# RunningAnalyzer_v1.net
KiCad netlist of a schematic drawn in EAGLE
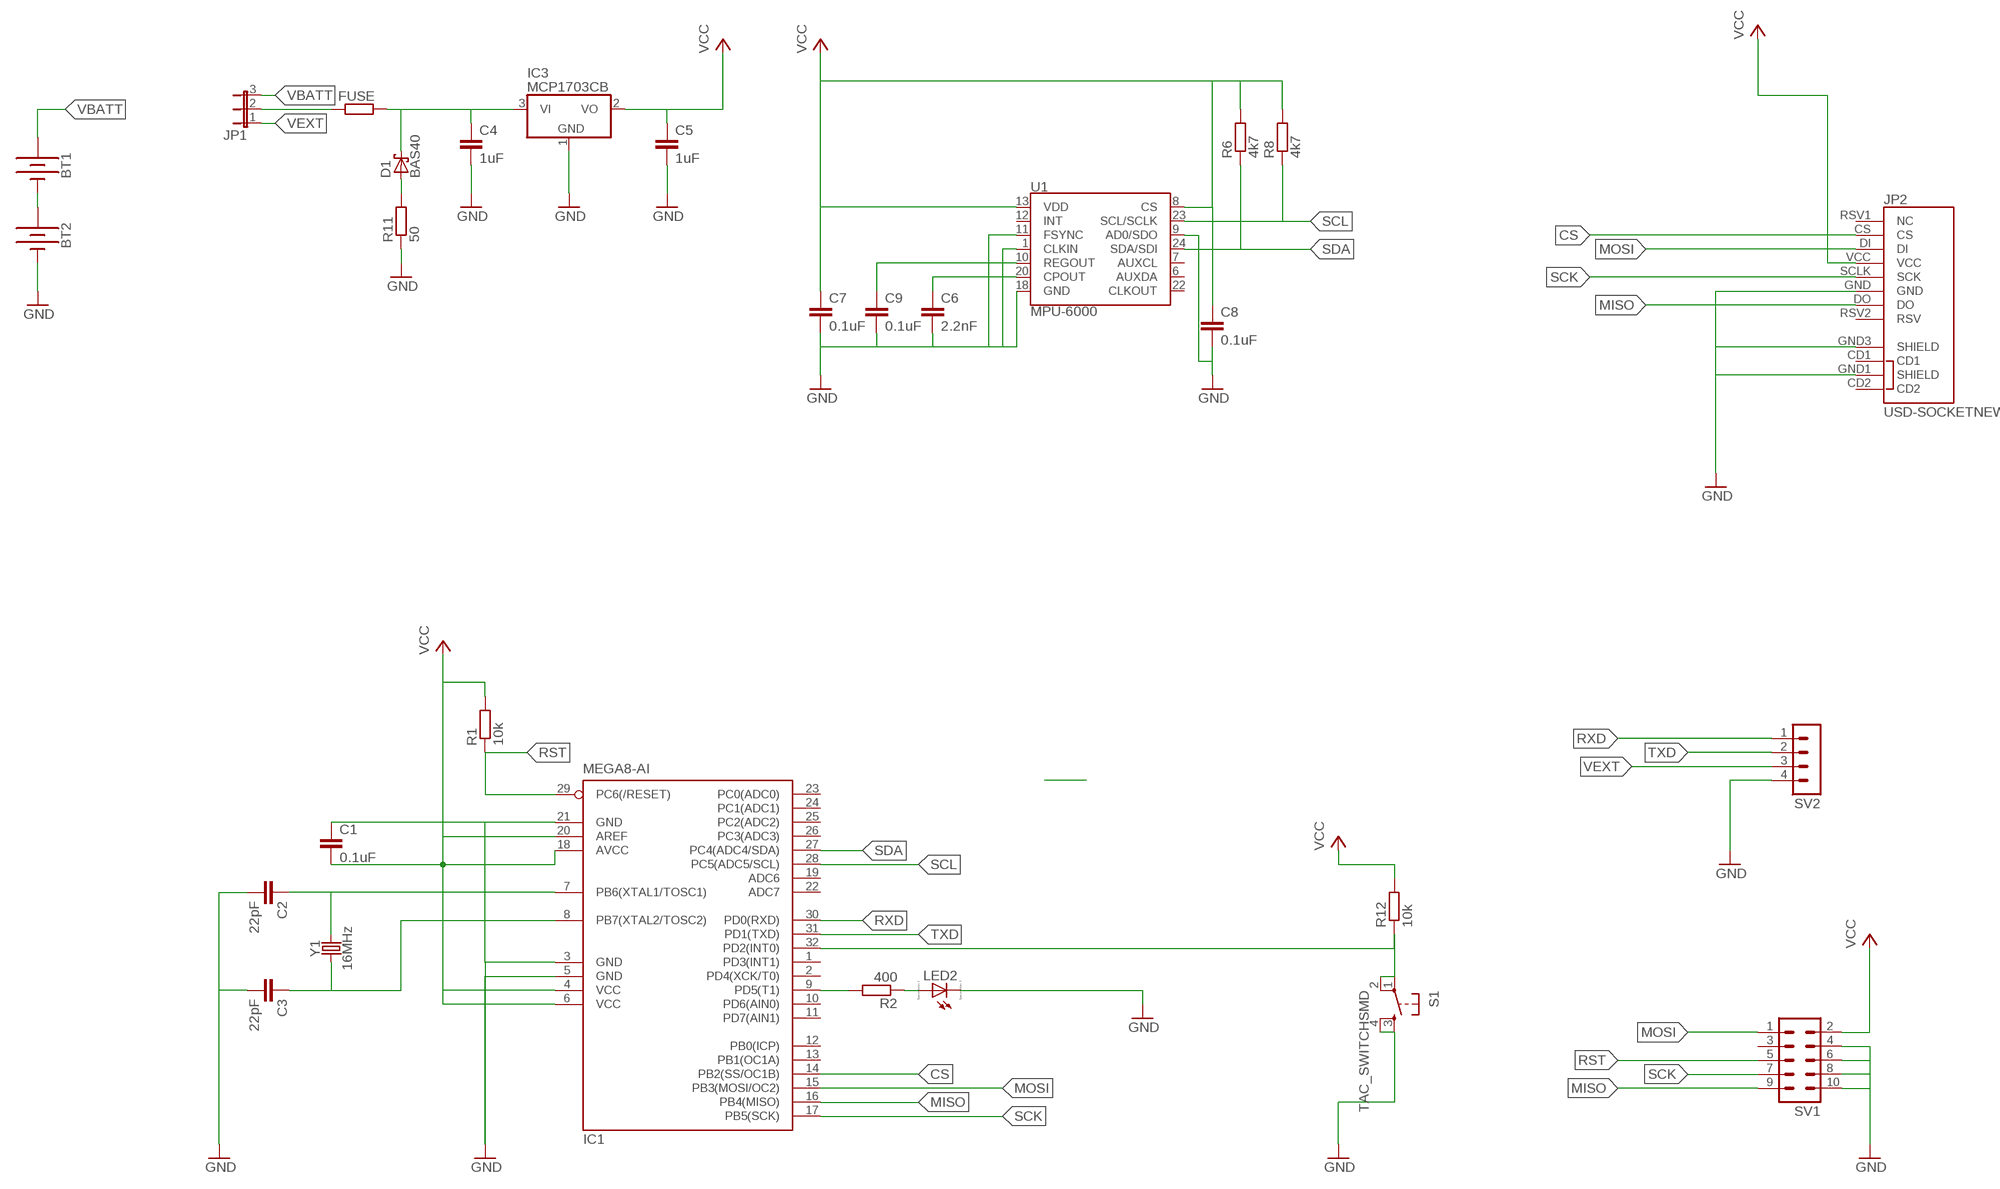
[diagram p0: schematic, sheet 1]

(export (version "E")
  (design (tool "Eeschema 10.0.6"))
  (components
    (comp (ref "BT1")
      (value "BATTERY-20MM_SMD_4LEGS_OVERPASTE")
      (footprint "eagle-import:BATTCON_20MM_4LEGS_OVERPASTE")
      (libsource (lib "eagle-import") (part "BATTERY-20MM_SMD_4LEGS_OVERPASTE"))
    )
    (comp (ref "BT2")
      (value "BATTERY-20MM_SMD_4LEGS_OVERPASTE")
      (footprint "eagle-import:BATTCON_20MM_4LEGS_OVERPASTE")
      (libsource (lib "eagle-import") (part "BATTERY-20MM_SMD_4LEGS_OVERPASTE"))
    )
    (comp (ref "C1")
      (value "0.1uF")
      (footprint "eagle-import:C0805")
      (libsource (lib "eagle-import") (part "C-EUC0805"))
    )
    (comp (ref "C2")
      (value "22pF")
      (footprint "eagle-import:C0805")
      (libsource (lib "eagle-import") (part "C-EUC0805"))
    )
    (comp (ref "C3")
      (value "22pF")
      (footprint "eagle-import:C0805")
      (libsource (lib "eagle-import") (part "C-EUC0805"))
    )
    (comp (ref "C4")
      (value "1uF")
      (footprint "eagle-import:C0805")
      (libsource (lib "eagle-import") (part "C-EUC0805"))
    )
    (comp (ref "C5")
      (value "1uF")
      (footprint "eagle-import:C0805")
      (libsource (lib "eagle-import") (part "C-EUC0805"))
    )
    (comp (ref "C6")
      (value "2.2nF")
      (footprint "eagle-import:C0805")
      (libsource (lib "eagle-import") (part "C-EUC0805"))
    )
    (comp (ref "C7")
      (value "0.1uF")
      (footprint "eagle-import:C0805")
      (libsource (lib "eagle-import") (part "C-EUC0805"))
    )
    (comp (ref "C8")
      (value "0.1uF")
      (footprint "eagle-import:C0805")
      (libsource (lib "eagle-import") (part "C-EUC0805"))
    )
    (comp (ref "C9")
      (value "0.1uF")
      (footprint "eagle-import:C0805")
      (libsource (lib "eagle-import") (part "C-EUC0805"))
    )
    (comp (ref "D1")
      (value "BAS40")
      (footprint "eagle-import:SOT23")
      (libsource (lib "eagle-import") (part "BAS40"))
    )
    (comp (ref "FUSE")
      (value "R-EU_M1206")
      (footprint "eagle-import:M1206")
      (libsource (lib "eagle-import") (part "R-EU_M1206"))
    )
    (comp (ref "IC1")
      (value "MEGA8-AI")
      (footprint "eagle-import:TQFP32-08")
      (fields (field (name "MPN") "ATMEGA8-16AU"))
      (libsource (lib "eagle-import") (part "MEGA8-AI"))
    )
    (comp (ref "IC3")
      (value "MCP1703CB")
      (footprint "eagle-import:SOT23")
      (libsource (lib "eagle-import") (part "MCP1703CB"))
    )
    (comp (ref "JP1")
      (value "JP2E")
      (footprint "eagle-import:JP2")
      (libsource (lib "eagle-import") (part "JP2E"))
    )
    (comp (ref "JP2")
      (value "USD-SOCKETNEW")
      (footprint "eagle-import:MICRO-SD-SOCKET-PP")
      (libsource (lib "eagle-import") (part "USD-SOCKETNEW"))
    )
    (comp (ref "LED2")
      (value "LED_E")
      (footprint "eagle-import:LED_1206")
      (libsource (lib "eagle-import") (part "LED_E"))
    )
    (comp (ref "R1")
      (value "10k")
      (footprint "eagle-import:R1206")
      (libsource (lib "eagle-import") (part "resistor_348_R-EU_R1206"))
    )
    (comp (ref "R2")
      (value "400")
      (footprint "eagle-import:R0805")
      (libsource (lib "eagle-import") (part "R-EU_R0805"))
    )
    (comp (ref "R6")
      (value "4k7")
      (footprint "eagle-import:R0805")
      (libsource (lib "eagle-import") (part "R-EU_R0805"))
    )
    (comp (ref "R8")
      (value "4k7")
      (footprint "eagle-import:R0805")
      (libsource (lib "eagle-import") (part "R-EU_R0805"))
    )
    (comp (ref "R11")
      (value "50")
      (footprint "eagle-import:R0805")
      (libsource (lib "eagle-import") (part "R-EU_R0805"))
    )
    (comp (ref "R12")
      (value "10k")
      (footprint "eagle-import:R1206")
      (libsource (lib "eagle-import") (part "resistor_348_R-EU_R1206"))
    )
    (comp (ref "S1")
      (value "TAC_SWITCHSMD")
      (footprint "eagle-import:TACTILE-SWITCH-SMD")
      (libsource (lib "eagle-import") (part "TAC_SWITCHSMD"))
    )
    (comp (ref "SV1")
      (value "MA05-2")
      (footprint "eagle-import:MA05-2")
      (libsource (lib "eagle-import") (part "MA05-2"))
    )
    (comp (ref "SV2")
      (value "MA04-1")
      (footprint "eagle-import:MA04-1")
      (libsource (lib "eagle-import") (part "MA04-1"))
    )
    (comp (ref "U1")
      (value "MPU-6000")
      (footprint "eagle-import:QFN-24-EP")
      (libsource (lib "eagle-import") (part "MPU-6000"))
    )
    (comp (ref "Y1")
      (value "16MHz")
      (footprint "eagle-import:HC49UP")
      (libsource (lib "eagle-import") (part "CRYSTALSMD-HC49UP"))
    )
  )
  (nets
    (net (code "1") (name "CS") (class "Default")
      (node (ref "IC1") (pin "14") (pinfunction "PB2(SS/OC1B)_14") (pintype "bidirectional"))
      (node (ref "JP2") (pin "CS") (pinfunction "CS_CS") (pintype "bidirectional"))
    )
    (net (code "2") (name "GND") (class "Default")
      (node (ref "BT2") (pin "2") (pinfunction "-_2") (pintype "power_in"))
      (node (ref "C1") (pin "1") (pinfunction "1_1") (pintype "passive"))
      (node (ref "C2") (pin "2") (pinfunction "2_2") (pintype "passive"))
      (node (ref "C3") (pin "2") (pinfunction "2_2") (pintype "passive"))
      (node (ref "C4") (pin "2") (pinfunction "2_2") (pintype "passive"))
      (node (ref "C5") (pin "2") (pinfunction "2_2") (pintype "passive"))
      (node (ref "C6") (pin "2") (pinfunction "2_2") (pintype "passive"))
      (node (ref "C7") (pin "2") (pinfunction "2_2") (pintype "passive"))
      (node (ref "C8") (pin "2") (pinfunction "2_2") (pintype "passive"))
      (node (ref "C9") (pin "2") (pinfunction "2_2") (pintype "passive"))
      (node (ref "IC1") (pin "21") (pinfunction "GND_21") (pintype "power_in"))
      (node (ref "IC1") (pin "3") (pinfunction "GND_3") (pintype "power_in"))
      (node (ref "IC1") (pin "5") (pinfunction "GND_5") (pintype "power_in"))
      (node (ref "IC3") (pin "1") (pinfunction "GND_1") (pintype "passive"))
      (node (ref "JP2") (pin "GND") (pinfunction "GND_GND") (pintype "bidirectional"))
      (node (ref "JP2") (pin "GND1") (pinfunction "SHIELD_GND1") (pintype "bidirectional"))
      (node (ref "JP2") (pin "GND3") (pinfunction "SHIELD_GND3") (pintype "bidirectional"))
      (node (ref "LED2") (pin "C") (pinfunction "C_C") (pintype "passive"))
      (node (ref "R11") (pin "1") (pinfunction "1_1") (pintype "passive"))
      (node (ref "S1") (pin "3") (pinfunction "3_3") (pintype "passive"))
      (node (ref "S1") (pin "4") (pinfunction "4_4") (pintype "passive"))
      (node (ref "SV1") (pin "10") (pinfunction "10_10") (pintype "passive"))
      (node (ref "SV1") (pin "4") (pinfunction "4_4") (pintype "passive"))
      (node (ref "SV1") (pin "6") (pinfunction "6_6") (pintype "passive"))
      (node (ref "SV1") (pin "8") (pinfunction "8_8") (pintype "passive"))
      (node (ref "SV2") (pin "4") (pinfunction "4_4") (pintype "passive"))
      (node (ref "U1") (pin "1") (pinfunction "CLKIN_1") (pintype "bidirectional"))
      (node (ref "U1") (pin "11") (pinfunction "FSYNC_11") (pintype "bidirectional"))
      (node (ref "U1") (pin "18") (pinfunction "GND_18") (pintype "bidirectional"))
      (node (ref "U1") (pin "9") (pinfunction "AD0/SDO_9") (pintype "bidirectional"))
    )
    (net (code "3") (name "MISO") (class "Default")
      (node (ref "IC1") (pin "16") (pinfunction "PB4(MISO)_16") (pintype "bidirectional"))
      (node (ref "JP2") (pin "DO") (pinfunction "DO_DO") (pintype "bidirectional"))
      (node (ref "SV1") (pin "9") (pinfunction "9_9") (pintype "passive"))
    )
    (net (code "4") (name "MOSI") (class "Default")
      (node (ref "IC1") (pin "15") (pinfunction "PB3(MOSI/OC2)_15") (pintype "bidirectional"))
      (node (ref "JP2") (pin "DI") (pinfunction "DI_DI") (pintype "bidirectional"))
      (node (ref "SV1") (pin "1") (pinfunction "1_1") (pintype "passive"))
    )
    (net (code "5") (name "Net-(BT1--)") (class "Default")
      (node (ref "BT1") (pin "2") (pinfunction "-_2") (pintype "power_in"))
      (node (ref "BT2") (pin "1") (pinfunction "+_1") (pintype "power_in"))
    )
    (net (code "6") (name "Net-(D1-A)") (class "Default")
      (node (ref "D1") (pin "1") (pinfunction "A_1") (pintype "passive"))
      (node (ref "R11") (pin "2") (pinfunction "2_2") (pintype "passive"))
    )
    (net (code "7") (name "Net-(D1-C)") (class "Default")
      (node (ref "C4") (pin "1") (pinfunction "1_1") (pintype "passive"))
      (node (ref "D1") (pin "3") (pinfunction "C_3") (pintype "passive"))
      (node (ref "FUSE") (pin "2") (pinfunction "2_2") (pintype "passive"))
      (node (ref "IC3") (pin "3") (pinfunction "VI_3") (pintype "input"))
    )
    (net (code "8") (name "Net-(FUSE-Pad1)") (class "Default")
      (node (ref "FUSE") (pin "1") (pinfunction "1_1") (pintype "passive"))
      (node (ref "JP1") (pin "2") (pinfunction "2_2") (pintype "passive"))
    )
    (net (code "9") (name "Net-(IC1-PB6(XTAL1{slash}TOSC1))") (class "Default")
      (node (ref "C2") (pin "1") (pinfunction "1_1") (pintype "passive"))
      (node (ref "IC1") (pin "7") (pinfunction "PB6(XTAL1/TOSC1)_7") (pintype "bidirectional"))
      (node (ref "Y1") (pin "2") (pinfunction "2_2") (pintype "passive"))
    )
    (net (code "10") (name "Net-(IC1-PB7(XTAL2{slash}TOSC2))") (class "Default")
      (node (ref "C3") (pin "1") (pinfunction "1_1") (pintype "passive"))
      (node (ref "IC1") (pin "8") (pinfunction "PB7(XTAL2/TOSC2)_8") (pintype "bidirectional"))
      (node (ref "Y1") (pin "1") (pinfunction "1_1") (pintype "passive"))
    )
    (net (code "11") (name "Net-(IC1-PD2(INT0))") (class "Default")
      (node (ref "IC1") (pin "32") (pinfunction "PD2(INT0)_32") (pintype "bidirectional"))
      (node (ref "R12") (pin "1") (pinfunction "1_1") (pintype "passive"))
      (node (ref "S1") (pin "1") (pinfunction "1_1") (pintype "passive"))
      (node (ref "S1") (pin "2") (pinfunction "2_2") (pintype "passive"))
    )
    (net (code "12") (name "Net-(IC1-PD5(T1))") (class "Default")
      (node (ref "IC1") (pin "9") (pinfunction "PD5(T1)_9") (pintype "bidirectional"))
      (node (ref "R2") (pin "2") (pinfunction "2_2") (pintype "passive"))
    )
    (net (code "13") (name "Net-(LED2-PadA)") (class "Default")
      (node (ref "LED2") (pin "A") (pinfunction "A_A") (pintype "passive"))
      (node (ref "R2") (pin "1") (pinfunction "1_1") (pintype "passive"))
    )
    (net (code "14") (name "Net-(U1-CPOUT)") (class "Default")
      (node (ref "C6") (pin "1") (pinfunction "1_1") (pintype "passive"))
      (node (ref "U1") (pin "20") (pinfunction "CPOUT_20") (pintype "bidirectional"))
    )
    (net (code "15") (name "Net-(U1-REGOUT)") (class "Default")
      (node (ref "C9") (pin "1") (pinfunction "1_1") (pintype "passive"))
      (node (ref "U1") (pin "10") (pinfunction "REGOUT_10") (pintype "bidirectional"))
    )
    (net (code "16") (name "RST") (class "Default")
      (node (ref "IC1") (pin "29") (pinfunction "PC6(/RESET)_29") (pintype "bidirectional"))
      (node (ref "R1") (pin "1") (pinfunction "1_1") (pintype "passive"))
      (node (ref "SV1") (pin "5") (pinfunction "5_5") (pintype "passive"))
    )
    (net (code "17") (name "RXD") (class "Default")
      (node (ref "IC1") (pin "30") (pinfunction "PD0(RXD)_30") (pintype "bidirectional"))
      (node (ref "SV2") (pin "1") (pinfunction "1_1") (pintype "passive"))
    )
    (net (code "18") (name "SCK") (class "Default")
      (node (ref "IC1") (pin "17") (pinfunction "PB5(SCK)_17") (pintype "bidirectional"))
      (node (ref "JP2") (pin "SCLK") (pinfunction "SCK_SCLK") (pintype "bidirectional"))
      (node (ref "SV1") (pin "7") (pinfunction "7_7") (pintype "passive"))
    )
    (net (code "19") (name "SCL") (class "Default")
      (node (ref "IC1") (pin "28") (pinfunction "PC5(ADC5/SCL)_28") (pintype "bidirectional"))
      (node (ref "R8") (pin "1") (pinfunction "1_1") (pintype "passive"))
      (node (ref "U1") (pin "23") (pinfunction "SCL/SCLK_23") (pintype "bidirectional"))
    )
    (net (code "20") (name "SDA") (class "Default")
      (node (ref "IC1") (pin "27") (pinfunction "PC4(ADC4/SDA)_27") (pintype "bidirectional"))
      (node (ref "R6") (pin "1") (pinfunction "1_1") (pintype "passive"))
      (node (ref "U1") (pin "24") (pinfunction "SDA/SDI_24") (pintype "bidirectional"))
    )
    (net (code "21") (name "TXD") (class "Default")
      (node (ref "IC1") (pin "31") (pinfunction "PD1(TXD)_31") (pintype "bidirectional"))
      (node (ref "SV2") (pin "2") (pinfunction "2_2") (pintype "passive"))
    )
    (net (code "22") (name "VBATT") (class "Default")
      (node (ref "BT1") (pin "1") (pinfunction "+_1") (pintype "power_in"))
      (node (ref "JP1") (pin "3") (pinfunction "3_3") (pintype "passive"))
    )
    (net (code "23") (name "VCC") (class "Default")
      (node (ref "C1") (pin "2") (pinfunction "2_2") (pintype "passive"))
      (node (ref "C5") (pin "1") (pinfunction "1_1") (pintype "passive"))
      (node (ref "C7") (pin "1") (pinfunction "1_1") (pintype "passive"))
      (node (ref "C8") (pin "1") (pinfunction "1_1") (pintype "passive"))
      (node (ref "IC1") (pin "18") (pinfunction "AVCC_18") (pintype "power_in"))
      (node (ref "IC1") (pin "20") (pinfunction "AREF_20") (pintype "passive"))
      (node (ref "IC1") (pin "4") (pinfunction "VCC_4") (pintype "power_in"))
      (node (ref "IC1") (pin "6") (pinfunction "VCC_6") (pintype "power_in"))
      (node (ref "IC3") (pin "2") (pinfunction "VO_2") (pintype "passive"))
      (node (ref "JP2") (pin "VCC") (pinfunction "VCC_VCC") (pintype "bidirectional"))
      (node (ref "R1") (pin "2") (pinfunction "2_2") (pintype "passive"))
      (node (ref "R12") (pin "2") (pinfunction "2_2") (pintype "passive"))
      (node (ref "R6") (pin "2") (pinfunction "2_2") (pintype "passive"))
      (node (ref "R8") (pin "2") (pinfunction "2_2") (pintype "passive"))
      (node (ref "SV1") (pin "2") (pinfunction "2_2") (pintype "passive"))
      (node (ref "U1") (pin "13") (pinfunction "VDD_13") (pintype "bidirectional"))
      (node (ref "U1") (pin "8") (pinfunction "CS_8") (pintype "bidirectional"))
    )
    (net (code "24") (name "VEXT") (class "Default")
      (node (ref "JP1") (pin "1") (pinfunction "1_1") (pintype "passive"))
      (node (ref "SV2") (pin "3") (pinfunction "3_3") (pintype "passive"))
    )
    (net (code "25") (name "unconnected-(IC1-ADC6-Pad19)") (class "Default")
      (node (ref "IC1") (pin "19") (pinfunction "ADC6_19") (pintype "bidirectional"))
    )
    (net (code "26") (name "unconnected-(IC1-ADC7-Pad22)") (class "Default")
      (node (ref "IC1") (pin "22") (pinfunction "ADC7_22") (pintype "bidirectional"))
    )
    (net (code "27") (name "unconnected-(IC1-PB0(ICP)-Pad12)") (class "Default")
      (node (ref "IC1") (pin "12") (pinfunction "PB0(ICP)_12") (pintype "bidirectional"))
    )
    (net (code "28") (name "unconnected-(IC1-PB1(OC1A)-Pad13)") (class "Default")
      (node (ref "IC1") (pin "13") (pinfunction "PB1(OC1A)_13") (pintype "bidirectional"))
    )
    (net (code "29") (name "unconnected-(IC1-PC0(ADC0)-Pad23)") (class "Default")
      (node (ref "IC1") (pin "23") (pinfunction "PC0(ADC0)_23") (pintype "bidirectional"))
    )
    (net (code "30") (name "unconnected-(IC1-PC1(ADC1)-Pad24)") (class "Default")
      (node (ref "IC1") (pin "24") (pinfunction "PC1(ADC1)_24") (pintype "bidirectional"))
    )
    (net (code "31") (name "unconnected-(IC1-PC2(ADC2)-Pad25)") (class "Default")
      (node (ref "IC1") (pin "25") (pinfunction "PC2(ADC2)_25") (pintype "bidirectional"))
    )
    (net (code "32") (name "unconnected-(IC1-PC3(ADC3)-Pad26)") (class "Default")
      (node (ref "IC1") (pin "26") (pinfunction "PC3(ADC3)_26") (pintype "bidirectional"))
    )
    (net (code "33") (name "unconnected-(IC1-PD3(INT1)-Pad1)") (class "Default")
      (node (ref "IC1") (pin "1") (pinfunction "PD3(INT1)_1") (pintype "bidirectional"))
    )
    (net (code "34") (name "unconnected-(IC1-PD4(XCK{slash}T0)-Pad2)") (class "Default")
      (node (ref "IC1") (pin "2") (pinfunction "PD4(XCK/T0)_2") (pintype "bidirectional"))
    )
    (net (code "35") (name "unconnected-(IC1-PD6(AIN0)-Pad10)") (class "Default")
      (node (ref "IC1") (pin "10") (pinfunction "PD6(AIN0)_10") (pintype "bidirectional"))
    )
    (net (code "36") (name "unconnected-(IC1-PD7(AIN1)-Pad11)") (class "Default")
      (node (ref "IC1") (pin "11") (pinfunction "PD7(AIN1)_11") (pintype "bidirectional"))
    )
    (net (code "37") (name "unconnected-(JP2-NC-PadRSV1)") (class "Default")
      (node (ref "JP2") (pin "RSV1") (pinfunction "NC_RSV1") (pintype "bidirectional"))
    )
    (net (code "38") (name "unconnected-(JP2-PadCD1)") (class "Default")
      (node (ref "JP2") (pin "CD1") (pinfunction "CD1_CD1") (pintype "bidirectional"))
    )
    (net (code "39") (name "unconnected-(JP2-PadCD2)") (class "Default")
      (node (ref "JP2") (pin "CD2") (pinfunction "CD2_CD2") (pintype "bidirectional"))
    )
    (net (code "40") (name "unconnected-(JP2-RSV-PadRSV2)") (class "Default")
      (node (ref "JP2") (pin "RSV2") (pinfunction "RSV_RSV2") (pintype "bidirectional"))
    )
    (net (code "41") (name "unconnected-(SV1-Pad3)") (class "Default")
      (node (ref "SV1") (pin "3") (pinfunction "3_3") (pintype "passive"))
    )
    (net (code "42") (name "unconnected-(U1-AUXCL-Pad7)") (class "Default")
      (node (ref "U1") (pin "7") (pinfunction "AUXCL_7") (pintype "bidirectional"))
    )
    (net (code "43") (name "unconnected-(U1-AUXDA-Pad6)") (class "Default")
      (node (ref "U1") (pin "6") (pinfunction "AUXDA_6") (pintype "bidirectional"))
    )
    (net (code "44") (name "unconnected-(U1-CLKOUT-Pad22)") (class "Default")
      (node (ref "U1") (pin "22") (pinfunction "CLKOUT_22") (pintype "bidirectional"))
    )
    (net (code "45") (name "unconnected-(U1-INT-Pad12)") (class "Default")
      (node (ref "U1") (pin "12") (pinfunction "INT_12") (pintype "bidirectional"))
    )
  )
)
